# Microcontroller.net
KiCad netlist of a schematic drawn in Altium Designer
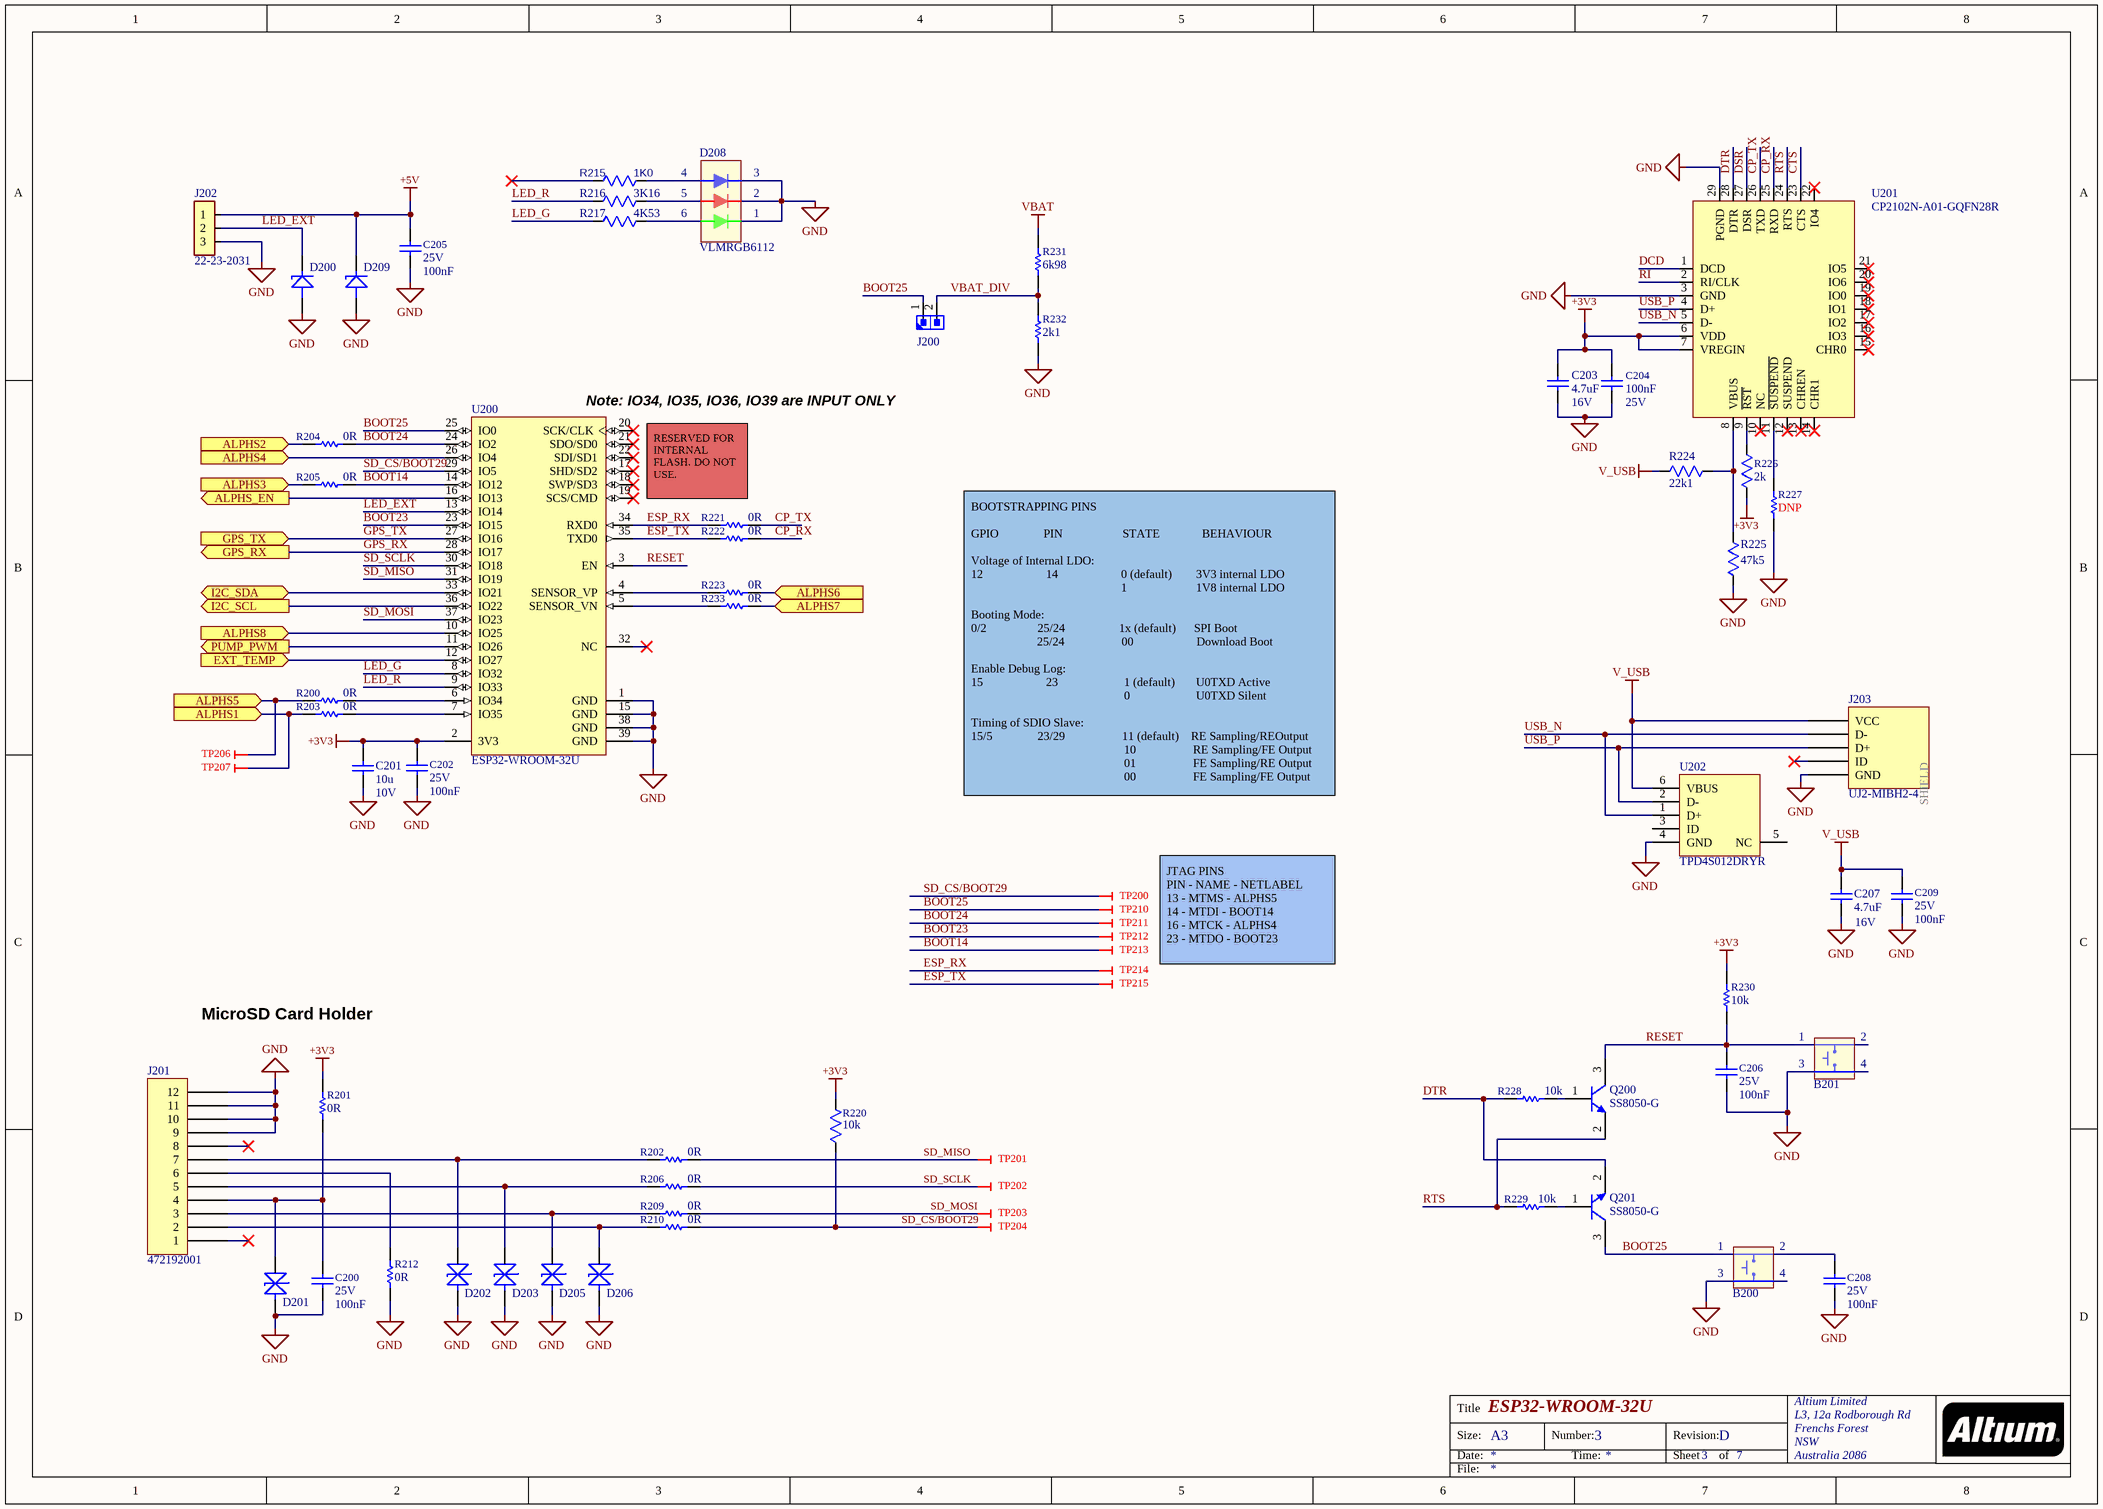
[diagram p0: Microcontroller.SchDoc]

(export (version "E")
  (design (tool "Eeschema 10.0.6"))
  (components
    (comp (ref "B200")
      (value "Button C&K PTS815 SJG 250 SMTR LFS")
      (footprint "PTS 815")
      (description "Push Button Top")
      (fields
        (field (name "MANUFACTURER") "C&K Components")
        (field (name "MANUFACTURER PART NUMBER") "PTS815 SJG 250 SMTR LFS")
      )
      (libsource (lib "Connectors") (part "Button C&K PTS815 SJG 250 SMTR LFS"))
    )
    (comp (ref "B201")
      (value "Button C&K PTS815 SJG 250 SMTR LFS")
      (footprint "PTS 815")
      (description "Push Button Top")
      (fields
        (field (name "MANUFACTURER") "C&K Components")
        (field (name "MANUFACTURER PART NUMBER") "PTS815 SJG 250 SMTR LFS")
      )
      (libsource (lib "Connectors") (part "Button C&K PTS815 SJG 250 SMTR LFS"))
    )
    (comp (ref "C200")
      (value "100nF")
      (footprint "CAPC1005X06N")
      (fields
        (field (name "VOLTAGE") "25V")
        (field (name "MANUFACTURER PART NUMBER") "CL05A104KA5NNNC")
        (field (name "MANUFACTURER") "Samsung")
        (field (name "Comment") "4.7uF")
      )
      (libsource (lib "Capacitors") (part "4.7uF_0603_10V"))
    )
    (comp (ref "C201")
      (value "10u")
      (footprint "CAPC1005X06N")
      (description "Capacitor")
      (fields
        (field (name "MANUFACTURER PART NUMBER") "CL05A106MP8NUB8")
        (field (name "MANUFACTURER") "Samsung")
        (field (name "VOLTAGE") "10V")
      )
      (libsource (lib "Santuary") (part "CAP{colon} GENERAL"))
    )
    (comp (ref "C202")
      (value "100nF")
      (footprint "CAPC1005X06N")
      (fields
        (field (name "VOLTAGE") "25V")
        (field (name "MANUFACTURER PART NUMBER") "CL05A104KA5NNNC")
        (field (name "MANUFACTURER") "Samsung")
        (field (name "Comment") "4.7uF")
      )
      (libsource (lib "Capacitors") (part "4.7uF_0603_10V"))
    )
    (comp (ref "C203")
      (value "4.7uF")
      (footprint "C1005[0402]")
      (description "Cap,4.7uF,10V,20%,X5R,0402")
      (fields
        (field (name "MANUFACTURER") "Samsung Electro-Mechanics")
        (field (name "MANUFACTURER PART NUMBER") "CL05A475MO5NUNC")
        (field (name "VOLTAGE") "16V")
      )
      (libsource (lib "Capacitors") (part "4.7uF_0402_10V"))
    )
    (comp (ref "C204")
      (value "100nF")
      (footprint "CAPC1005X06N")
      (fields
        (field (name "VOLTAGE") "25V")
        (field (name "MANUFACTURER PART NUMBER") "CL05A104KA5NNNC")
        (field (name "MANUFACTURER") "Samsung")
        (field (name "Comment") "4.7uF")
      )
      (libsource (lib "Capacitors") (part "4.7uF_0603_10V"))
    )
    (comp (ref "C205")
      (value "100nF")
      (footprint "CAPC1005X06N")
      (fields
        (field (name "VOLTAGE") "25V")
        (field (name "MANUFACTURER PART NUMBER") "CL05A104KA5NNNC")
        (field (name "MANUFACTURER") "Samsung")
        (field (name "Comment") "4.7uF")
      )
      (libsource (lib "Capacitors") (part "4.7uF_0603_10V"))
    )
    (comp (ref "C206")
      (value "100nF")
      (footprint "CAPC1005X06N")
      (fields
        (field (name "VOLTAGE") "25V")
        (field (name "MANUFACTURER PART NUMBER") "CL05A104KA5NNNC")
        (field (name "MANUFACTURER") "Samsung")
        (field (name "Comment") "4.7uF")
      )
      (libsource (lib "Capacitors") (part "4.7uF_0603_10V"))
    )
    (comp (ref "C207")
      (value "4.7uF")
      (footprint "C1005[0402]")
      (description "Cap,4.7uF,10V,20%,X5R,0402")
      (fields
        (field (name "MANUFACTURER") "Samsung Electro-Mechanics")
        (field (name "MANUFACTURER PART NUMBER") "CL05A475MO5NUNC")
        (field (name "VOLTAGE") "16V")
      )
      (libsource (lib "Capacitors") (part "4.7uF_0402_10V"))
    )
    (comp (ref "C208")
      (value "100nF")
      (footprint "CAPC1005X06N")
      (fields
        (field (name "VOLTAGE") "25V")
        (field (name "MANUFACTURER PART NUMBER") "CL05A104KA5NNNC")
        (field (name "MANUFACTURER") "Samsung")
        (field (name "Comment") "4.7uF")
      )
      (libsource (lib "Capacitors") (part "4.7uF_0603_10V"))
    )
    (comp (ref "C209")
      (value "100nF")
      (footprint "CAPC1005X06N")
      (fields
        (field (name "VOLTAGE") "25V")
        (field (name "MANUFACTURER PART NUMBER") "CL05A104KA5NNNC")
        (field (name "MANUFACTURER") "Samsung")
        (field (name "Comment") "4.7uF")
      )
      (libsource (lib "Capacitors") (part "4.7uF_0603_10V"))
    )
    (comp (ref "D200")
      (value "5V TVS")
      (footprint "NXP PTVSxS1UR-Series (SOD123W)")
      (fields
        (field (name "MANUFACTURER") "Nexperia")
        (field (name "MANUFACTURER PART NUMBER") "PTVS5V0S1UR,115")
      )
      (libsource (lib "FSM_2018") (part "NXP PTVSxS1UR-Series"))
    )
    (comp (ref "D201")
      (value "ESD7951ST5GOSCT-ND")
      (footprint "SODFL100X40-2N")
      (description "TVS Diode")
      (fields
        (field (name "MANUFACTURER PART NUMBER") "ESD7951ST5G")
        (field (name "MANUFACTURER") "ON Semiconductor")
      )
      (libsource (lib "Gas Monitor Components") (part "ESD7951S"))
    )
    (comp (ref "D202")
      (value "ESD7951ST5GOSCT-ND")
      (footprint "SODFL100X40-2N")
      (description "TVS Diode")
      (fields
        (field (name "MANUFACTURER PART NUMBER") "ESD7951ST5G")
        (field (name "MANUFACTURER") "ON Semiconductor")
      )
      (libsource (lib "Gas Monitor Components") (part "ESD7951S"))
    )
    (comp (ref "D203")
      (value "ESD7951ST5GOSCT-ND")
      (footprint "SODFL100X40-2N")
      (description "TVS Diode")
      (fields
        (field (name "MANUFACTURER PART NUMBER") "ESD7951ST5G")
        (field (name "MANUFACTURER") "ON Semiconductor")
      )
      (libsource (lib "Gas Monitor Components") (part "ESD7951S"))
    )
    (comp (ref "D205")
      (value "ESD7951ST5GOSCT-ND")
      (footprint "SODFL100X40-2N")
      (description "TVS Diode")
      (fields
        (field (name "MANUFACTURER PART NUMBER") "ESD7951ST5G")
        (field (name "MANUFACTURER") "ON Semiconductor")
      )
      (libsource (lib "Gas Monitor Components") (part "ESD7951S"))
    )
    (comp (ref "D206")
      (value "ESD7951ST5GOSCT-ND")
      (footprint "SODFL100X40-2N")
      (description "TVS Diode")
      (fields
        (field (name "MANUFACTURER PART NUMBER") "ESD7951ST5G")
        (field (name "MANUFACTURER") "ON Semiconductor")
      )
      (libsource (lib "Gas Monitor Components") (part "ESD7951S"))
    )
    (comp (ref "D208")
      (value "VLMRGB6112")
      (footprint "VLMRGB6112")
      (description "LED RGB Clear 624nm/526nm/469nm 2V/3.1V/3V PLCC-6")
      (fields
        (field (name "MANUFACTURER") "Vishay Semiconductor Opto Division")
        (field (name "MANUFACTURER PART NUMBER") "VLMRGB6112-00-GS08")
      )
      (libsource (lib "LEDs") (part "VLMRGB6112"))
    )
    (comp (ref "D209")
      (value "5V TVS")
      (footprint "NXP PTVSxS1UR-Series (SOD123W)")
      (fields
        (field (name "MANUFACTURER") "Nexperia")
        (field (name "MANUFACTURER PART NUMBER") "PTVS5V0S1UR,115")
      )
      (libsource (lib "FSM_2018") (part "NXP PTVSxS1UR-Series"))
    )
    (comp (ref "J200")
      (value "PRPC002SAAN-RC")
      (footprint "HDR_1x2_0.100\"")
      (description "CONN HEADER VERT 2POS 2.54MM")
      (fields (field (name "MANUFACTURER") "Sullins"))
      (libsource (lib "Gas Monitor Components") (part "PRPC002SAAN-RC"))
    )
    (comp (ref "J201")
      (value "472192001")
      (footprint "SD-47219-001")
      (fields (field (name "MANUFACTURER") "Molex") (field (name "MANUFACTURER PART NUMBER") "0472192001"))
      (libsource (lib "Gas Monitor Components") (part "CON12"))
    )
    (comp (ref "J202")
      (value "22-23-2031")
      (footprint "22-23-2031")
      (description "Connector Header Through Hole 3 position 0.100\" (2.54mm)")
      (fields (field (name "MANUFACTURER") "Molex") (field (name "MANUFACTURER PART NUMBER") "0022232031"))
      (libsource (lib "Gas Monitor Components") (part "22-23-2031"))
    )
    (comp (ref "J203")
      (value "UJ2-MIBH2-4")
      (footprint "UJ2-MIBH2-4-SMT")
      (fields
        (field (name "MANUFACTURER") "CUI")
        (field (name "MANUFACTURER PART NUMBER") "UJ2-MIBH2-4-SMT-TR")
      )
      (libsource (lib "Gas Monitor Components") (part "USB Shield"))
    )
    (comp (ref "Q200")
      (value "SS8050-G")
      (footprint "ONSC-SOT-23-3-318-08_V")
      (description "General Purpose Transistor, NPN Silicon, 3-Pin SOT-23, Tape and Reel")
      (fields (field (name "MANUFACTURER") "Comchip Technology"))
      (libsource (lib "Altium Content Vault") (part "ONSC-NPN-B1E2C3-3"))
    )
    (comp (ref "Q201")
      (value "SS8050-G")
      (footprint "ONSC-SOT-23-3-318-08_V")
      (description "General Purpose Transistor, NPN Silicon, 3-Pin SOT-23, Tape and Reel")
      (fields (field (name "MANUFACTURER") "Comchip Technology"))
      (libsource (lib "Altium Content Vault") (part "ONSC-NPN-B1E2C3-3"))
    )
    (comp (ref "R200")
      (value "0R")
      (footprint "RESC1005X03N")
      (fields
        (field (name "MANUFACTURER") "Panasonic")
        (field (name "MANUFACTURER PART NUMBER") "ERJ-2GE0R00X")
        (field (name "Comment") "RES: GENERAL")
      )
      (libsource (lib "Santuary") (part "RES{colon} GENERAL"))
    )
    (comp (ref "R201")
      (value "0R")
      (footprint "RESC1005X03N")
      (fields
        (field (name "MANUFACTURER") "Panasonic")
        (field (name "MANUFACTURER PART NUMBER") "ERJ-2GE0R00X")
        (field (name "Comment") "RES: GENERAL")
      )
      (libsource (lib "Santuary") (part "RES{colon} GENERAL"))
    )
    (comp (ref "R202")
      (value "0R")
      (footprint "RESC1005X03N")
      (fields
        (field (name "MANUFACTURER") "Panasonic")
        (field (name "MANUFACTURER PART NUMBER") "ERJ-2GE0R00X")
        (field (name "Comment") "RES: GENERAL")
      )
      (libsource (lib "Santuary") (part "RES{colon} GENERAL"))
    )
    (comp (ref "R203")
      (value "0R")
      (footprint "RESC1005X03N")
      (fields
        (field (name "MANUFACTURER") "Panasonic")
        (field (name "MANUFACTURER PART NUMBER") "ERJ-2GE0R00X")
        (field (name "Comment") "RES: GENERAL")
      )
      (libsource (lib "Santuary") (part "RES{colon} GENERAL"))
    )
    (comp (ref "R204")
      (value "0R")
      (footprint "RESC1005X03N")
      (fields
        (field (name "MANUFACTURER") "Panasonic")
        (field (name "MANUFACTURER PART NUMBER") "ERJ-2GE0R00X")
        (field (name "Comment") "RES: GENERAL")
      )
      (libsource (lib "Santuary") (part "RES{colon} GENERAL"))
    )
    (comp (ref "R205")
      (value "0R")
      (footprint "RESC1005X03N")
      (fields
        (field (name "MANUFACTURER") "Panasonic")
        (field (name "MANUFACTURER PART NUMBER") "ERJ-2GE0R00X")
        (field (name "Comment") "RES: GENERAL")
      )
      (libsource (lib "Santuary") (part "RES{colon} GENERAL"))
    )
    (comp (ref "R206")
      (value "0R")
      (footprint "RESC1005X03N")
      (fields
        (field (name "MANUFACTURER") "Panasonic")
        (field (name "MANUFACTURER PART NUMBER") "ERJ-2GE0R00X")
        (field (name "Comment") "RES: GENERAL")
      )
      (libsource (lib "Santuary") (part "RES{colon} GENERAL"))
    )
    (comp (ref "R209")
      (value "0R")
      (footprint "RESC1005X03N")
      (fields
        (field (name "MANUFACTURER") "Panasonic")
        (field (name "MANUFACTURER PART NUMBER") "ERJ-2GE0R00X")
        (field (name "Comment") "RES: GENERAL")
      )
      (libsource (lib "Santuary") (part "RES{colon} GENERAL"))
    )
    (comp (ref "R210")
      (value "0R")
      (footprint "RESC1005X03N")
      (fields
        (field (name "MANUFACTURER") "Panasonic")
        (field (name "MANUFACTURER PART NUMBER") "ERJ-2GE0R00X")
        (field (name "Comment") "RES: GENERAL")
      )
      (libsource (lib "Santuary") (part "RES{colon} GENERAL"))
    )
    (comp (ref "R212")
      (value "0R")
      (footprint "RESC1005X03N")
      (fields
        (field (name "MANUFACTURER") "Panasonic")
        (field (name "MANUFACTURER PART NUMBER") "ERJ-2GE0R00X")
        (field (name "Comment") "RES: GENERAL")
      )
      (libsource (lib "Santuary") (part "RES{colon} GENERAL"))
    )
    (comp (ref "R215")
      (value "1K0")
      (footprint "RESC1005X03N")
      (description "RES 1K Ohm ±5%, 0.25W,1/4W 0603")
      (fields
        (field (name "MANUFACTURER") "Panasonic")
        (field (name "MANUFACTURER PART NUMBER") "ERJ-2RKF1001X")
      )
      (libsource (lib "Resistors") (part "1K00_0603_0.1W"))
    )
    (comp (ref "R216")
      (value "3K16")
      (footprint "RESC1005X03N")
      (description "Res,SMD,1/10W,3K16,0603,1%")
      (fields
        (field (name "MANUFACTURER") "Stackpole Electronics")
        (field (name "MANUFACTURER PART NUMBER") "RMCF0603FT3K16")
      )
      (libsource (lib "Resistors") (part "3K16_Resistor_0603"))
    )
    (comp (ref "R217")
      (value "4K53")
      (footprint "RESC1005X03N")
      (description "Res,SMD,4K53,1/10W,1%,0603")
      (fields
        (field (name "MANUFACTURER") "Yageo")
        (field (name "MANUFACTURER PART NUMBER") "RC0603FR-074K53L")
      )
      (libsource (lib "Resistors") (part "4K53_Resistor_0603"))
    )
    (comp (ref "R220")
      (value "10k")
      (footprint "RESC1005X03N")
      (description "RES 10k Ohm")
      (fields
        (field (name "MANUFACTURER") "Panasonic")
        (field (name "MANUFACTURER PART NUMBER") "ERJ-2RKF1002X")
      )
      (libsource (lib "Resistors") (part "1K00_0603_0.1W"))
    )
    (comp (ref "R221")
      (value "0R")
      (footprint "RESC1005X03N")
      (fields
        (field (name "MANUFACTURER") "Panasonic")
        (field (name "MANUFACTURER PART NUMBER") "ERJ-2GE0R00X")
        (field (name "Comment") "RES: GENERAL")
      )
      (libsource (lib "Santuary") (part "RES{colon} GENERAL"))
    )
    (comp (ref "R222")
      (value "0R")
      (footprint "RESC1005X03N")
      (fields
        (field (name "MANUFACTURER") "Panasonic")
        (field (name "MANUFACTURER PART NUMBER") "ERJ-2GE0R00X")
        (field (name "Comment") "RES: GENERAL")
      )
      (libsource (lib "Santuary") (part "RES{colon} GENERAL"))
    )
    (comp (ref "R223")
      (value "0R")
      (footprint "RESC1005X03N")
      (fields
        (field (name "MANUFACTURER") "Panasonic")
        (field (name "MANUFACTURER PART NUMBER") "ERJ-2GE0R00X")
        (field (name "Comment") "RES: GENERAL")
      )
      (libsource (lib "Santuary") (part "RES{colon} GENERAL"))
    )
    (comp (ref "R224")
      (value "22k1")
      (footprint "R1005[0402]")
      (description "Res,SMD,22k,0603,5%,1/4W")
      (fields
        (field (name "MANUFACTURER PART NUMBER") "ERJ-2RKF2212X")
        (field (name "MANUFACTURER") "Panasonic")
      )
      (libsource (lib "Resistors") (part "22K_0603_1/4W"))
    )
    (comp (ref "R225")
      (value "47k5")
      (footprint "R1005[0402]")
      (description "Res,SMD,22k,0603,5%,1/4W")
      (fields
        (field (name "MANUFACTURER PART NUMBER") "ERJ-2RKF4752X")
        (field (name "MANUFACTURER") "Panasonic")
      )
      (libsource (lib "Resistors") (part "22K_0603_1/4W"))
    )
    (comp (ref "R226")
      (value "2k")
      (footprint "R1005[0402]")
      (fields
        (field (name "MANUFACTURER") "Panasonic")
        (field (name "MANUFACTURER PART NUMBER") "ERJ-2RKF2001X")
        (field (name "Comment") "10K")
      )
      (libsource (lib "Resistors") (part "1K00_0603_0.1W"))
    )
    (comp (ref "R227")
      (value "DNP")
      (footprint "RESC1005X03N")
      (fields (field (name "Comment") "RES: GENERAL"))
      (libsource (lib "Santuary") (part "RES{colon} GENERAL"))
    )
    (comp (ref "R228")
      (value "10k")
      (footprint "RESC1005X03N")
      (fields
        (field (name "MANUFACTURER") "Panasonic")
        (field (name "MANUFACTURER PART NUMBER") "ERJ-2RKF1002X")
        (field (name "Comment") "RES: GENERAL")
      )
      (libsource (lib "Santuary") (part "RES{colon} GENERAL"))
    )
    (comp (ref "R229")
      (value "10k")
      (footprint "RESC1005X03N")
      (fields
        (field (name "MANUFACTURER") "Panasonic")
        (field (name "MANUFACTURER PART NUMBER") "ERJ-2RKF1002X")
        (field (name "Comment") "RES: GENERAL")
      )
      (libsource (lib "Santuary") (part "RES{colon} GENERAL"))
    )
    (comp (ref "R230")
      (value "10k")
      (footprint "RESC1005X03N")
      (fields
        (field (name "MANUFACTURER") "Panasonic")
        (field (name "MANUFACTURER PART NUMBER") "ERJ-2RKF1002X")
        (field (name "Comment") "RES: GENERAL")
      )
      (libsource (lib "Santuary") (part "RES{colon} GENERAL"))
    )
    (comp (ref "R231")
      (value "6k98")
      (footprint "RESC1005X03N")
      (fields
        (field (name "MANUFACTURER") "Panasonic")
        (field (name "MANUFACTURER PART NUMBER") "ERJ-2RKF6981X")
        (field (name "Comment") "RES: GENERAL")
      )
      (libsource (lib "Santuary") (part "RES{colon} GENERAL"))
    )
    (comp (ref "R232")
      (value "2k1")
      (footprint "RESC1005X03N")
      (fields
        (field (name "MANUFACTURER") "Panasonic")
        (field (name "MANUFACTURER PART NUMBER") "ERJ-2RKF2101X")
        (field (name "Comment") "RES: GENERAL")
      )
      (libsource (lib "Santuary") (part "RES{colon} GENERAL"))
    )
    (comp (ref "R233")
      (value "0R")
      (footprint "RESC1005X03N")
      (fields
        (field (name "MANUFACTURER") "Panasonic")
        (field (name "MANUFACTURER PART NUMBER") "ERJ-2GE0R00X")
        (field (name "Comment") "RES: GENERAL")
      )
      (libsource (lib "Santuary") (part "RES{colon} GENERAL"))
    )
    (comp (ref "TP200")
      (value "PAD")
      (footprint "TP_SMD_39MIL")
      (description "SMD Test Pad")
      (fields (field (name "MANUFACTURER") "No P/N Required"))
      (libsource (lib "Connectors") (part "TP_SMD_39MIL"))
    )
    (comp (ref "TP201")
      (value "PAD")
      (footprint "TP_SMD_39MIL")
      (description "SMD Test Pad")
      (fields (field (name "MANUFACTURER") "No P/N Required"))
      (libsource (lib "Connectors") (part "TP_SMD_39MIL"))
    )
    (comp (ref "TP202")
      (value "PAD")
      (footprint "TP_SMD_39MIL")
      (description "SMD Test Pad")
      (fields (field (name "MANUFACTURER") "No P/N Required"))
      (libsource (lib "Connectors") (part "TP_SMD_39MIL"))
    )
    (comp (ref "TP203")
      (value "PAD")
      (footprint "TP_SMD_39MIL")
      (description "SMD Test Pad")
      (fields (field (name "MANUFACTURER") "No P/N Required"))
      (libsource (lib "Connectors") (part "TP_SMD_39MIL"))
    )
    (comp (ref "TP204")
      (value "PAD")
      (footprint "TP_SMD_39MIL")
      (description "SMD Test Pad")
      (fields (field (name "MANUFACTURER") "No P/N Required"))
      (libsource (lib "Connectors") (part "TP_SMD_39MIL"))
    )
    (comp (ref "TP206")
      (value "PAD")
      (footprint "TP_SMD_39MIL")
      (description "SMD Test Pad")
      (fields (field (name "MANUFACTURER") "No P/N Required"))
      (libsource (lib "Connectors") (part "TP_SMD_39MIL"))
    )
    (comp (ref "TP207")
      (value "PAD")
      (footprint "TP_SMD_39MIL")
      (description "SMD Test Pad")
      (fields (field (name "MANUFACTURER") "No P/N Required"))
      (libsource (lib "Connectors") (part "TP_SMD_39MIL"))
    )
    (comp (ref "TP210")
      (value "PAD")
      (footprint "TP_SMD_39MIL")
      (description "SMD Test Pad")
      (fields (field (name "MANUFACTURER") "No P/N Required"))
      (libsource (lib "Connectors") (part "TP_SMD_39MIL"))
    )
    (comp (ref "TP211")
      (value "PAD")
      (footprint "TP_SMD_39MIL")
      (description "SMD Test Pad")
      (fields (field (name "MANUFACTURER") "No P/N Required"))
      (libsource (lib "Connectors") (part "TP_SMD_39MIL"))
    )
    (comp (ref "TP212")
      (value "PAD")
      (footprint "TP_SMD_39MIL")
      (description "SMD Test Pad")
      (fields (field (name "MANUFACTURER") "No P/N Required"))
      (libsource (lib "Connectors") (part "TP_SMD_39MIL"))
    )
    (comp (ref "TP213")
      (value "PAD")
      (footprint "TP_SMD_39MIL")
      (description "SMD Test Pad")
      (fields (field (name "MANUFACTURER") "No P/N Required"))
      (libsource (lib "Connectors") (part "TP_SMD_39MIL"))
    )
    (comp (ref "TP214")
      (value "PAD")
      (footprint "TP_SMD_39MIL")
      (description "SMD Test Pad")
      (fields (field (name "MANUFACTURER") "No P/N Required"))
      (libsource (lib "Connectors") (part "TP_SMD_39MIL"))
    )
    (comp (ref "TP215")
      (value "PAD")
      (footprint "TP_SMD_39MIL")
      (description "SMD Test Pad")
      (fields (field (name "MANUFACTURER") "No P/N Required"))
      (libsource (lib "Connectors") (part "TP_SMD_39MIL"))
    )
    (comp (ref "U200")
      (value "ESP32-WROOM-32U")
      (footprint "ESP32-WROOM-32U")
      (description "Microcontroller WIFI Module 32Mbits SPI Flash")
      (fields (field (name "MANUFACTURER") "Espressif Systems"))
      (libsource (lib "Gas Monitor Components") (part "ESP32-WROOM-32U"))
    )
    (comp (ref "U201")
      (value "CP2102N-A01-GQFN28R")
      (footprint "QFN50P500X500X80_HS-29N")
      (description "USB to UART converter")
      (fields (field (name "MANUFACTURER") "Silicon Labs"))
      (libsource (lib "ICs-V") (part "CP2102N QFN28"))
    )
    (comp (ref "U202")
      (value "TPD4S012DRYR")
      (footprint "DRY0006A")
      (fields (field (name "MANUFACTURER") "Texas Instruments"))
      (libsource (lib "Altium Content Vault") (part "TI-TPD4S012-SON_DRY-6"))
    )
  )
  (nets
    (net (code "1") (name "+3V3") (class "Default")
      (node (ref "C201") (pin "2") (pinfunction "2_2") (pintype "passive"))
      (node (ref "C202") (pin "1") (pintype "passive"))
      (node (ref "C203") (pin "2") (pintype "passive"))
      (node (ref "C204") (pin "1") (pintype "passive"))
      (node (ref "R201") (pin "1") (pinfunction "1_1") (pintype "passive"))
      (node (ref "R220") (pin "2") (pintype "passive"))
      (node (ref "R226") (pin "1") (pintype "passive"))
      (node (ref "R230") (pin "1") (pinfunction "1_1") (pintype "passive"))
      (node (ref "U200") (pin "2") (pinfunction "3V3_2") (pintype "power_in"))
      (node (ref "U201") (pin "6") (pinfunction "VDD_6") (pintype "power_in"))
      (node (ref "U201") (pin "7") (pinfunction "VREGIN_7") (pintype "power_in"))
    )
    (net (code "2") (name "+5V") (class "Default")
      (node (ref "C205") (pin "1") (pintype "passive"))
      (node (ref "D209") (pin "1") (pinfunction "1_1") (pintype "passive"))
      (node (ref "J202") (pin "1") (pinfunction "1_1") (pintype "passive"))
    )
    (net (code "3") (name "/ALPHS1") (class "Default")
      (node (ref "R203") (pin "2") (pinfunction "2_2") (pintype "passive"))
      (node (ref "TP207") (pin "1") (pintype "passive"))
    )
    (net (code "4") (name "/ALPHS2") (class "Default")
      (node (ref "R204") (pin "2") (pinfunction "2_2") (pintype "passive"))
    )
    (net (code "5") (name "/ALPHS3") (class "Default")
      (node (ref "R205") (pin "2") (pinfunction "2_2") (pintype "passive"))
    )
    (net (code "6") (name "/ALPHS4") (class "Default")
      (node (ref "U200") (pin "26") (pinfunction "IO4_26") (pintype "bidirectional"))
    )
    (net (code "7") (name "/ALPHS5") (class "Default")
      (node (ref "R200") (pin "2") (pinfunction "2_2") (pintype "passive"))
      (node (ref "TP206") (pin "1") (pintype "passive"))
    )
    (net (code "8") (name "/ALPHS6") (class "Default")
      (node (ref "R223") (pin "1") (pinfunction "1_1") (pintype "passive"))
    )
    (net (code "9") (name "/ALPHS7") (class "Default")
      (node (ref "R233") (pin "1") (pinfunction "1_1") (pintype "passive"))
    )
    (net (code "10") (name "/ALPHS8") (class "Default")
      (node (ref "U200") (pin "10") (pinfunction "IO25_10") (pintype "bidirectional"))
    )
    (net (code "11") (name "/ALPHS_EN") (class "Default")
      (node (ref "U200") (pin "16") (pinfunction "IO13_16") (pintype "bidirectional"))
    )
    (net (code "12") (name "/BOOT14") (class "Default")
      (node (ref "R205") (pin "1") (pinfunction "1_1") (pintype "passive"))
      (node (ref "TP213") (pin "1") (pintype "passive"))
      (node (ref "U200") (pin "14") (pinfunction "IO12_14") (pintype "bidirectional"))
    )
    (net (code "13") (name "/BOOT23") (class "Default")
      (node (ref "TP212") (pin "1") (pintype "passive"))
      (node (ref "U200") (pin "23") (pinfunction "IO15_23") (pintype "bidirectional"))
    )
    (net (code "14") (name "/BOOT24") (class "Default")
      (node (ref "R204") (pin "1") (pinfunction "1_1") (pintype "passive"))
      (node (ref "TP211") (pin "1") (pintype "passive"))
      (node (ref "U200") (pin "24") (pinfunction "IO2_24") (pintype "bidirectional"))
    )
    (net (code "15") (name "/BOOT25") (class "Default")
      (node (ref "B200") (pin "1") (pinfunction "1_1") (pintype "passive"))
      (node (ref "J200") (pin "1") (pinfunction "1_1") (pintype "passive"))
      (node (ref "Q201") (pin "3") (pinfunction "C_3") (pintype "passive"))
      (node (ref "TP210") (pin "1") (pintype "passive"))
      (node (ref "U200") (pin "25") (pinfunction "IO0_25") (pintype "bidirectional"))
    )
    (net (code "16") (name "/CP_RX") (class "Default")
      (node (ref "R222") (pin "1") (pinfunction "1_1") (pintype "passive"))
      (node (ref "U201") (pin "25") (pinfunction "RXD_25") (pintype "passive"))
    )
    (net (code "17") (name "/CP_TX") (class "Default")
      (node (ref "R221") (pin "1") (pinfunction "1_1") (pintype "passive"))
      (node (ref "U201") (pin "26") (pinfunction "TXD_26") (pintype "passive"))
    )
    (net (code "18") (name "/CTS") (class "Default")
      (node (ref "U201") (pin "23") (pinfunction "CTS_23") (pintype "passive"))
    )
    (net (code "19") (name "/DCD") (class "Default")
      (node (ref "U201") (pin "1") (pinfunction "DCD_1") (pintype "passive"))
    )
    (net (code "20") (name "/DSR") (class "Default")
      (node (ref "U201") (pin "27") (pinfunction "DSR_27") (pintype "passive"))
    )
    (net (code "21") (name "/DTR") (class "Default")
      (node (ref "Q201") (pin "2") (pinfunction "E_2") (pintype "passive"))
      (node (ref "R228") (pin "2") (pinfunction "2_2") (pintype "passive"))
      (node (ref "U201") (pin "28") (pinfunction "DTR_28") (pintype "passive"))
    )
    (net (code "22") (name "/ESP_RX") (class "Default")
      (node (ref "R221") (pin "2") (pinfunction "2_2") (pintype "passive"))
      (node (ref "TP214") (pin "1") (pintype "passive"))
      (node (ref "U200") (pin "34") (pinfunction "RXD0_34") (pintype "input"))
    )
    (net (code "23") (name "/ESP_TX") (class "Default")
      (node (ref "R222") (pin "2") (pinfunction "2_2") (pintype "passive"))
      (node (ref "TP215") (pin "1") (pintype "passive"))
      (node (ref "U200") (pin "35") (pinfunction "TXD0_35") (pintype "output"))
    )
    (net (code "24") (name "/EXT_TEMP") (class "Default")
      (node (ref "U200") (pin "12") (pinfunction "IO27_12") (pintype "bidirectional"))
    )
    (net (code "25") (name "/GPS_RX") (class "Default")
      (node (ref "U200") (pin "28") (pinfunction "IO17_28") (pintype "bidirectional"))
    )
    (net (code "26") (name "/GPS_TX") (class "Default")
      (node (ref "U200") (pin "27") (pinfunction "IO16_27") (pintype "bidirectional"))
    )
    (net (code "27") (name "/I2C_SCL") (class "Default")
      (node (ref "U200") (pin "36") (pinfunction "IO22_36") (pintype "bidirectional"))
    )
    (net (code "28") (name "/I2C_SDA") (class "Default")
      (node (ref "U200") (pin "33") (pinfunction "IO21_33") (pintype "bidirectional"))
    )
    (net (code "29") (name "/LED_EXT") (class "Default")
      (node (ref "D200") (pin "1") (pinfunction "1_1") (pintype "passive"))
      (node (ref "J202") (pin "2") (pinfunction "2_2") (pintype "passive"))
      (node (ref "U200") (pin "13") (pinfunction "IO14_13") (pintype "bidirectional"))
    )
    (net (code "30") (name "/LED_G") (class "Default")
      (node (ref "R217") (pin "1") (pintype "passive"))
      (node (ref "U200") (pin "8") (pinfunction "IO32_8") (pintype "bidirectional"))
    )
    (net (code "31") (name "/LED_R") (class "Default")
      (node (ref "R216") (pin "1") (pintype "passive"))
      (node (ref "U200") (pin "9") (pinfunction "IO33_9") (pintype "bidirectional"))
    )
    (net (code "32") (name "/PUMP_PWM") (class "Default")
      (node (ref "U200") (pin "11") (pinfunction "IO26_11") (pintype "bidirectional"))
    )
    (net (code "33") (name "/RESET") (class "Default")
      (node (ref "B201") (pin "1") (pinfunction "1_1") (pintype "passive"))
      (node (ref "C206") (pin "1") (pintype "passive"))
      (node (ref "Q200") (pin "3") (pinfunction "C_3") (pintype "passive"))
      (node (ref "R230") (pin "2") (pinfunction "2_2") (pintype "passive"))
      (node (ref "U200") (pin "3") (pinfunction "EN_3") (pintype "input"))
    )
    (net (code "34") (name "/RI") (class "Default")
      (node (ref "U201") (pin "2") (pinfunction "RI/CLK_2") (pintype "passive"))
    )
    (net (code "35") (name "/RTS") (class "Default")
      (node (ref "Q200") (pin "2") (pinfunction "E_2") (pintype "passive"))
      (node (ref "R229") (pin "2") (pinfunction "2_2") (pintype "passive"))
      (node (ref "U201") (pin "24") (pinfunction "RTS_24") (pintype "passive"))
    )
    (net (code "36") (name "/SD_CS{slash}BOOT29") (class "Default")
      (node (ref "R210") (pin "1") (pinfunction "1_1") (pintype "passive"))
      (node (ref "R220") (pin "1") (pintype "passive"))
      (node (ref "TP200") (pin "1") (pintype "passive"))
      (node (ref "TP204") (pin "1") (pintype "passive"))
      (node (ref "U200") (pin "29") (pinfunction "IO5_29") (pintype "bidirectional"))
    )
    (net (code "37") (name "/SD_MISO") (class "Default")
      (node (ref "R202") (pin "1") (pinfunction "1_1") (pintype "passive"))
      (node (ref "TP201") (pin "1") (pintype "passive"))
      (node (ref "U200") (pin "31") (pinfunction "IO19_31") (pintype "bidirectional"))
    )
    (net (code "38") (name "/SD_MOSI") (class "Default")
      (node (ref "R209") (pin "1") (pinfunction "1_1") (pintype "passive"))
      (node (ref "TP203") (pin "1") (pintype "passive"))
      (node (ref "U200") (pin "37") (pinfunction "IO23_37") (pintype "bidirectional"))
    )
    (net (code "39") (name "/SD_SCLK") (class "Default")
      (node (ref "R206") (pin "1") (pinfunction "1_1") (pintype "passive"))
      (node (ref "TP202") (pin "1") (pintype "passive"))
      (node (ref "U200") (pin "30") (pinfunction "IO18_30") (pintype "bidirectional"))
    )
    (net (code "40") (name "/USB_N") (class "Default")
      (node (ref "J203") (pin "2") (pinfunction "D-_2") (pintype "passive"))
      (node (ref "U201") (pin "5") (pinfunction "D-_5") (pintype "passive"))
      (node (ref "U202") (pin "1") (pinfunction "D+_1") (pintype "passive"))
    )
    (net (code "41") (name "/USB_P") (class "Default")
      (node (ref "J203") (pin "3") (pinfunction "D+_3") (pintype "passive"))
      (node (ref "U201") (pin "4") (pinfunction "D+_4") (pintype "passive"))
      (node (ref "U202") (pin "2") (pinfunction "D-_2") (pintype "passive"))
    )
    (net (code "42") (name "/VBAT_DIV") (class "Default")
      (node (ref "J200") (pin "2") (pinfunction "2_2") (pintype "passive"))
      (node (ref "R231") (pin "2") (pinfunction "2_2") (pintype "passive"))
      (node (ref "R232") (pin "1") (pinfunction "1_1") (pintype "passive"))
    )
    (net (code "43") (name "GND") (class "Default")
      (node (ref "B200") (pin "3") (pinfunction "3_3") (pintype "passive"))
      (node (ref "B201") (pin "3") (pinfunction "3_3") (pintype "passive"))
      (node (ref "C200") (pin "2") (pintype "passive"))
      (node (ref "C201") (pin "1") (pinfunction "1_1") (pintype "passive"))
      (node (ref "C202") (pin "2") (pintype "passive"))
      (node (ref "C203") (pin "1") (pintype "passive"))
      (node (ref "C204") (pin "2") (pintype "passive"))
      (node (ref "C205") (pin "2") (pintype "passive"))
      (node (ref "C206") (pin "2") (pintype "passive"))
      (node (ref "C207") (pin "1") (pintype "passive"))
      (node (ref "C208") (pin "2") (pintype "passive"))
      (node (ref "C209") (pin "2") (pintype "passive"))
      (node (ref "D200") (pin "2") (pinfunction "2_2") (pintype "passive"))
      (node (ref "D201") (pin "1") (pinfunction "CATHODE_1") (pintype "passive"))
      (node (ref "D202") (pin "1") (pinfunction "CATHODE_1") (pintype "passive"))
      (node (ref "D203") (pin "1") (pinfunction "CATHODE_1") (pintype "passive"))
      (node (ref "D205") (pin "1") (pinfunction "CATHODE_1") (pintype "passive"))
      (node (ref "D206") (pin "1") (pinfunction "CATHODE_1") (pintype "passive"))
      (node (ref "D208") (pin "1") (pinfunction "A2_1") (pintype "passive"))
      (node (ref "D208") (pin "2") (pinfunction "C3_2") (pintype "passive"))
      (node (ref "D208") (pin "3") (pinfunction "A3_3") (pintype "passive"))
      (node (ref "D209") (pin "2") (pinfunction "2_2") (pintype "passive"))
      (node (ref "J201") (pin "10") (pinfunction "10_10") (pintype "passive"))
      (node (ref "J201") (pin "11") (pinfunction "11_11") (pintype "passive"))
      (node (ref "J201") (pin "12") (pinfunction "12_12") (pintype "passive"))
      (node (ref "J201") (pin "9") (pinfunction "9_9") (pintype "passive"))
      (node (ref "J202") (pin "3") (pinfunction "3_3") (pintype "passive"))
      (node (ref "J203") (pin "5") (pinfunction "GND_5") (pintype "power_in"))
      (node (ref "R212") (pin "2") (pinfunction "2_2") (pintype "passive"))
      (node (ref "R225") (pin "1") (pintype "passive"))
      (node (ref "R227") (pin "2") (pinfunction "2_2") (pintype "passive"))
      (node (ref "R232") (pin "2") (pinfunction "2_2") (pintype "passive"))
      (node (ref "U200") (pin "1") (pinfunction "GND_1") (pintype "power_in"))
      (node (ref "U200") (pin "15") (pinfunction "GND_15") (pintype "power_in"))
      (node (ref "U200") (pin "38") (pinfunction "GND_38") (pintype "power_in"))
      (node (ref "U200") (pin "39") (pinfunction "GND_39") (pintype "power_in"))
      (node (ref "U201") (pin "29") (pinfunction "PGND_29") (pintype "passive"))
      (node (ref "U201") (pin "3") (pinfunction "GND_3") (pintype "power_in"))
      (node (ref "U202") (pin "4") (pinfunction "GND_4") (pintype "power_in"))
    )
    (net (code "44") (name "Net-(B200-Pad2)") (class "Default")
      (node (ref "B200") (pin "2") (pinfunction "2_2") (pintype "passive"))
      (node (ref "C208") (pin "1") (pintype "passive"))
    )
    (net (code "45") (name "Net-(D201-ANODE)") (class "Default")
      (node (ref "C200") (pin "1") (pintype "passive"))
      (node (ref "D201") (pin "2") (pinfunction "ANODE_2") (pintype "passive"))
      (node (ref "J201") (pin "4") (pinfunction "4_4") (pintype "passive"))
      (node (ref "R201") (pin "2") (pinfunction "2_2") (pintype "passive"))
    )
    (net (code "46") (name "Net-(D202-ANODE)") (class "Default")
      (node (ref "D202") (pin "2") (pinfunction "ANODE_2") (pintype "passive"))
      (node (ref "J201") (pin "7") (pinfunction "7_7") (pintype "passive"))
      (node (ref "R202") (pin "2") (pinfunction "2_2") (pintype "passive"))
    )
    (net (code "47") (name "Net-(D203-ANODE)") (class "Default")
      (node (ref "D203") (pin "2") (pinfunction "ANODE_2") (pintype "passive"))
      (node (ref "J201") (pin "5") (pinfunction "5_5") (pintype "passive"))
      (node (ref "R206") (pin "2") (pinfunction "2_2") (pintype "passive"))
    )
    (net (code "48") (name "Net-(D205-ANODE)") (class "Default")
      (node (ref "D205") (pin "2") (pinfunction "ANODE_2") (pintype "passive"))
      (node (ref "J201") (pin "3") (pinfunction "3_3") (pintype "passive"))
      (node (ref "R209") (pin "2") (pinfunction "2_2") (pintype "passive"))
    )
    (net (code "49") (name "Net-(D206-ANODE)") (class "Default")
      (node (ref "D206") (pin "2") (pinfunction "ANODE_2") (pintype "passive"))
      (node (ref "J201") (pin "2") (pinfunction "2_2") (pintype "passive"))
      (node (ref "R210") (pin "2") (pinfunction "2_2") (pintype "passive"))
    )
    (net (code "50") (name "Net-(D208-C1-Pad4)") (class "Default")
      (node (ref "D208") (pin "4") (pinfunction "C1_4") (pintype "passive"))
      (node (ref "R215") (pin "2") (pintype "passive"))
    )
    (net (code "51") (name "Net-(D208-C1-Pad5)") (class "Default")
      (node (ref "D208") (pin "5") (pinfunction "C1_5") (pintype "passive"))
      (node (ref "R216") (pin "2") (pintype "passive"))
    )
    (net (code "52") (name "Net-(D208-C1-Pad6)") (class "Default")
      (node (ref "D208") (pin "6") (pinfunction "C1_6") (pintype "passive"))
      (node (ref "R217") (pin "2") (pintype "passive"))
    )
    (net (code "53") (name "Net-(J201-Pad6)") (class "Default")
      (node (ref "J201") (pin "6") (pinfunction "6_6") (pintype "passive"))
      (node (ref "R212") (pin "1") (pinfunction "1_1") (pintype "passive"))
    )
    (net (code "54") (name "Net-(Q200-B)") (class "Default")
      (node (ref "Q200") (pin "1") (pinfunction "B_1") (pintype "passive"))
      (node (ref "R228") (pin "1") (pinfunction "1_1") (pintype "passive"))
    )
    (net (code "55") (name "Net-(Q201-B)") (class "Default")
      (node (ref "Q201") (pin "1") (pinfunction "B_1") (pintype "passive"))
      (node (ref "R229") (pin "1") (pinfunction "1_1") (pintype "passive"))
    )
    (net (code "56") (name "Net-(U200-IO34)") (class "Default")
      (node (ref "R200") (pin "1") (pinfunction "1_1") (pintype "passive"))
      (node (ref "U200") (pin "6") (pinfunction "IO34_6") (pintype "input"))
    )
    (net (code "57") (name "Net-(U200-IO35)") (class "Default")
      (node (ref "R203") (pin "1") (pinfunction "1_1") (pintype "passive"))
      (node (ref "U200") (pin "7") (pinfunction "IO35_7") (pintype "input"))
    )
    (net (code "58") (name "Net-(U200-SENSOR_VN)") (class "Default")
      (node (ref "R233") (pin "2") (pinfunction "2_2") (pintype "passive"))
      (node (ref "U200") (pin "5") (pinfunction "SENSOR_VN_5") (pintype "input"))
    )
    (net (code "59") (name "Net-(U200-SENSOR_VP)") (class "Default")
      (node (ref "R223") (pin "2") (pinfunction "2_2") (pintype "passive"))
      (node (ref "U200") (pin "4") (pinfunction "SENSOR_VP_4") (pintype "input"))
    )
    (net (code "60") (name "Net-(U201-VBUS)") (class "Default")
      (node (ref "R224") (pin "2") (pintype "passive"))
      (node (ref "R225") (pin "2") (pintype "passive"))
      (node (ref "U201") (pin "8") (pinfunction "VBUS_8") (pintype "passive"))
    )
    (net (code "61") (name "Net-(U201-~{RST})") (class "Default")
      (node (ref "R226") (pin "2") (pintype "passive"))
      (node (ref "U201") (pin "9") (pinfunction "~{RST}_9") (pintype "passive"))
    )
    (net (code "62") (name "Net-(U201-~{SUSPEND})") (class "Default")
      (node (ref "R227") (pin "1") (pinfunction "1_1") (pintype "passive"))
      (node (ref "U201") (pin "11") (pinfunction "~{SUSPEND}_11") (pintype "passive"))
    )
    (net (code "63") (name "VBAT") (class "Default")
      (node (ref "R231") (pin "1") (pinfunction "1_1") (pintype "passive"))
    )
    (net (code "64") (name "V_USB") (class "Default")
      (node (ref "C207") (pin "2") (pintype "passive"))
      (node (ref "C209") (pin "1") (pintype "passive"))
      (node (ref "J203") (pin "1") (pinfunction "VCC_1") (pintype "power_in"))
      (node (ref "R224") (pin "1") (pintype "passive"))
      (node (ref "U202") (pin "6") (pinfunction "VBUS_6") (pintype "passive"))
    )
    (net (code "65") (name "unconnected-(B200-Pad4)") (class "Default")
      (node (ref "B200") (pin "4") (pinfunction "4_4") (pintype "passive"))
    )
    (net (code "66") (name "unconnected-(B201-Pad2)") (class "Default")
      (node (ref "B201") (pin "2") (pinfunction "2_2") (pintype "passive"))
    )
    (net (code "67") (name "unconnected-(B201-Pad4)") (class "Default")
      (node (ref "B201") (pin "4") (pinfunction "4_4") (pintype "passive"))
    )
    (net (code "68") (name "unconnected-(J201-Pad1)") (class "Default")
      (node (ref "J201") (pin "1") (pinfunction "1_1") (pintype "passive+no_connect"))
    )
    (net (code "69") (name "unconnected-(J201-Pad8)") (class "Default")
      (node (ref "J201") (pin "8") (pinfunction "8_8") (pintype "passive+no_connect"))
    )
    (net (code "70") (name "unconnected-(J203-ID-Pad4)") (class "Default")
      (node (ref "J203") (pin "4") (pinfunction "ID_4") (pintype "passive+no_connect"))
    )
    (net (code "71") (name "unconnected-(R215-Pad1)") (class "Default")
      (node (ref "R215") (pin "1") (pintype "passive+no_connect"))
    )
    (net (code "72") (name "unconnected-(U200-NC-Pad32)") (class "Default")
      (node (ref "U200") (pin "32") (pinfunction "NC_32") (pintype "passive+no_connect"))
    )
    (net (code "73") (name "unconnected-(U200-SCK{slash}CLK-Pad20)") (class "Default")
      (node (ref "U200") (pin "20") (pinfunction "SCK/CLK_20") (pintype "bidirectional+no_connect"))
    )
    (net (code "74") (name "unconnected-(U200-SCS{slash}CMD-Pad19)") (class "Default")
      (node (ref "U200") (pin "19") (pinfunction "SCS/CMD_19") (pintype "bidirectional+no_connect"))
    )
    (net (code "75") (name "unconnected-(U200-SDI{slash}SD1-Pad22)") (class "Default")
      (node (ref "U200") (pin "22") (pinfunction "SDI/SD1_22") (pintype "bidirectional+no_connect"))
    )
    (net (code "76") (name "unconnected-(U200-SDO{slash}SD0-Pad21)") (class "Default")
      (node (ref "U200") (pin "21") (pinfunction "SDO/SD0_21") (pintype "bidirectional+no_connect"))
    )
    (net (code "77") (name "unconnected-(U200-SHD{slash}SD2-Pad17)") (class "Default")
      (node (ref "U200") (pin "17") (pinfunction "SHD/SD2_17") (pintype "bidirectional+no_connect"))
    )
    (net (code "78") (name "unconnected-(U200-SWP{slash}SD3-Pad18)") (class "Default")
      (node (ref "U200") (pin "18") (pinfunction "SWP/SD3_18") (pintype "bidirectional+no_connect"))
    )
    (net (code "79") (name "unconnected-(U201-CHR0-Pad15)") (class "Default")
      (node (ref "U201") (pin "15") (pinfunction "CHR0_15") (pintype "passive+no_connect"))
    )
    (net (code "80") (name "unconnected-(U201-CHR1-Pad14)") (class "Default")
      (node (ref "U201") (pin "14") (pinfunction "CHR1_14") (pintype "passive+no_connect"))
    )
    (net (code "81") (name "unconnected-(U201-CHREN-Pad13)") (class "Default")
      (node (ref "U201") (pin "13") (pinfunction "CHREN_13") (pintype "passive+no_connect"))
    )
    (net (code "82") (name "unconnected-(U201-IO0-Pad19)") (class "Default")
      (node (ref "U201") (pin "19") (pinfunction "IO0_19") (pintype "passive+no_connect"))
    )
    (net (code "83") (name "unconnected-(U201-IO1-Pad18)") (class "Default")
      (node (ref "U201") (pin "18") (pinfunction "IO1_18") (pintype "passive+no_connect"))
    )
    (net (code "84") (name "unconnected-(U201-IO2-Pad17)") (class "Default")
      (node (ref "U201") (pin "17") (pinfunction "IO2_17") (pintype "passive+no_connect"))
    )
    (net (code "85") (name "unconnected-(U201-IO3-Pad16)") (class "Default")
      (node (ref "U201") (pin "16") (pinfunction "IO3_16") (pintype "passive+no_connect"))
    )
    (net (code "86") (name "unconnected-(U201-IO4-Pad22)") (class "Default")
      (node (ref "U201") (pin "22") (pinfunction "IO4_22") (pintype "passive+no_connect"))
    )
    (net (code "87") (name "unconnected-(U201-IO5-Pad21)") (class "Default")
      (node (ref "U201") (pin "21") (pinfunction "IO5_21") (pintype "passive+no_connect"))
    )
    (net (code "88") (name "unconnected-(U201-IO6-Pad20)") (class "Default")
      (node (ref "U201") (pin "20") (pinfunction "IO6_20") (pintype "passive+no_connect"))
    )
    (net (code "89") (name "unconnected-(U201-NC-Pad10)") (class "Default")
      (node (ref "U201") (pin "10") (pinfunction "NC_10") (pintype "passive+no_connect"))
    )
    (net (code "90") (name "unconnected-(U201-SUSPEND-Pad12)") (class "Default")
      (node (ref "U201") (pin "12") (pinfunction "SUSPEND_12") (pintype "passive+no_connect"))
    )
    (net (code "91") (name "unconnected-(U202-ID-Pad3)") (class "Default")
      (node (ref "U202") (pin "3") (pinfunction "ID_3") (pintype "passive"))
    )
    (net (code "92") (name "unconnected-(U202-NC-Pad5)") (class "Default")
      (node (ref "U202") (pin "5") (pinfunction "NC_5") (pintype "passive"))
    )
  )
)
